# 8x3.net
KiCad netlist of a schematic drawn in Altium Designer
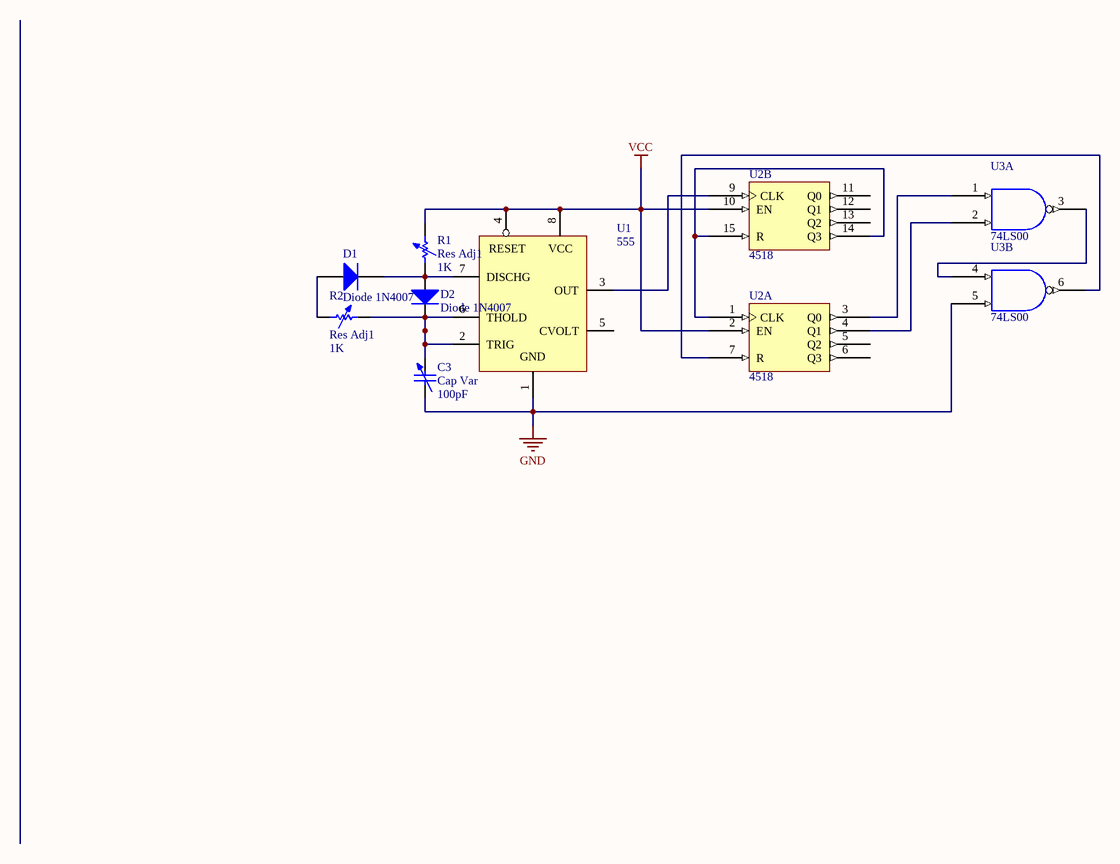
[diagram p0: 8x3.SchDoc]

(export (version "E")
  (design (tool "Eeschema 10.0.6"))
  (components
    (comp (ref "C3")
      (value "Cap Var")
      (footprint "C1210_N")
      (description "Variable or Adjustable Capacitor")
      (fields (field (name "ALTIUM_VALUE") "100pF") (field (name "PUBLISHER") "Altium Limited"))
      (libsource (lib "Miscellaneous Devices") (part "Cap Var"))
    )
    (comp (ref "D1")
      (value "Diode 1N4007")
      (footprint "DO-41")
      (description "1 Amp General Purpose Rectifier")
      (fields (field (name "PUBLISHER") "Altium Limited"))
      (libsource (lib "Miscellaneous Devices") (part "Diode 1N4007"))
    )
    (comp (ref "D2")
      (value "Diode 1N4007")
      (footprint "DO-41")
      (description "1 Amp General Purpose Rectifier")
      (fields (field (name "PUBLISHER") "Altium Limited"))
      (libsource (lib "Miscellaneous Devices") (part "Diode 1N4007"))
    )
    (comp (ref "R1")
      (value "Res Adj1")
      (footprint "AXIAL-0.7")
      (description "Variable Resistor")
      (fields (field (name "ALTIUM_VALUE") "1K") (field (name "PUBLISHER") "Altium Limited"))
      (libsource (lib "Miscellaneous Devices") (part "Res Adj1"))
    )
    (comp (ref "R2")
      (value "Res Adj1")
      (footprint "AXIAL-0.7")
      (description "Variable Resistor")
      (fields (field (name "ALTIUM_VALUE") "1K") (field (name "PUBLISHER") "Altium Limited"))
      (libsource (lib "Miscellaneous Devices") (part "Res Adj1"))
    )
    (comp (ref "U1") (value "555") (description "Timer") (libsource (lib "555") (part "555")))
    (comp (ref "U2") (value "4518") (footprint "DIP-16") (libsource (lib "CD4000系列IC") (part "4518")))
    (comp (ref "U3") (value "74LS00") (footprint "DIP-14") (libsource (lib "TTL74系列IC") (part "74LS00")))
  )
  (nets
    (net (code "1") (name "GND") (class "Default")
      (node (ref "C3") (pin "1") (pinfunction "1_1") (pintype "passive"))
      (node (ref "U1") (pin "1") (pinfunction "GND_1") (pintype "passive"))
      (node (ref "U2") (pin "8") (pinfunction "GND_8") (pintype "power_in"))
      (node (ref "U3") (pin "5") (pintype "input"))
      (node (ref "U3") (pin "7") (pinfunction "GND_7") (pintype "power_in"))
    )
    (net (code "2") (name "Net-(D1-A)") (class "Default")
      (node (ref "D1") (pin "1") (pinfunction "A_1") (pintype "passive"))
      (node (ref "R2") (pin "1") (pinfunction "1_1") (pintype "passive"))
    )
    (net (code "3") (name "Net-(D1-K)") (class "Default")
      (node (ref "D1") (pin "2") (pinfunction "K_2") (pintype "passive"))
      (node (ref "R1") (pin "1") (pinfunction "1_1") (pintype "passive"))
      (node (ref "U1") (pin "7") (pinfunction "DISCHG_7") (pintype "passive"))
    )
    (net (code "4") (name "Net-(D2-K)") (class "Default")
      (node (ref "C3") (pin "2") (pinfunction "2_2") (pintype "passive"))
      (node (ref "D2") (pin "2") (pinfunction "K_2") (pintype "passive"))
      (node (ref "R2") (pin "2") (pinfunction "2_2") (pintype "passive"))
      (node (ref "U1") (pin "2") (pinfunction "TRIG_2") (pintype "passive"))
      (node (ref "U1") (pin "6") (pinfunction "THOLD_6") (pintype "passive"))
    )
    (net (code "5") (name "Net-(U1-OUT)") (class "Default")
      (node (ref "U1") (pin "3") (pinfunction "OUT_3") (pintype "passive"))
      (node (ref "U2") (pin "9") (pinfunction "CLK_9") (pintype "input"))
    )
    (net (code "6") (name "Net-(U2A-CLK)") (class "Default")
      (node (ref "U2") (pin "1") (pinfunction "CLK_1") (pintype "input"))
      (node (ref "U2") (pin "14") (pinfunction "Q3_14") (pintype "output"))
      (node (ref "U2") (pin "15") (pinfunction "R_15") (pintype "input"))
    )
    (net (code "7") (name "Net-(U2A-Q0)") (class "Default")
      (node (ref "U2") (pin "3") (pinfunction "Q0_3") (pintype "output"))
      (node (ref "U3") (pin "1") (pintype "input"))
    )
    (net (code "8") (name "Net-(U2A-Q1)") (class "Default")
      (node (ref "U2") (pin "4") (pinfunction "Q1_4") (pintype "output"))
      (node (ref "U3") (pin "2") (pintype "input"))
    )
    (net (code "9") (name "Net-(U2A-R)") (class "Default")
      (node (ref "U2") (pin "7") (pinfunction "R_7") (pintype "input"))
      (node (ref "U3") (pin "6") (pintype "output"))
    )
    (net (code "10") (name "Net-(U3-Pad3)") (class "Default")
      (node (ref "U3") (pin "3") (pintype "output"))
      (node (ref "U3") (pin "4") (pintype "input"))
    )
    (net (code "11") (name "VCC") (class "Default")
      (node (ref "R1") (pin "2") (pinfunction "2_2") (pintype "passive"))
      (node (ref "U1") (pin "4") (pinfunction "RESET_4") (pintype "passive"))
      (node (ref "U1") (pin "8") (pinfunction "VCC_8") (pintype "passive"))
      (node (ref "U2") (pin "10") (pinfunction "EN_10") (pintype "input"))
      (node (ref "U2") (pin "16") (pinfunction "VCC_16") (pintype "power_in"))
      (node (ref "U2") (pin "2") (pinfunction "EN_2") (pintype "input"))
      (node (ref "U3") (pin "14") (pinfunction "VCC_14") (pintype "power_in"))
    )
    (net (code "12") (name "unconnected-(D2-A-Pad1)") (class "Default")
      (node (ref "D2") (pin "1") (pinfunction "A_1") (pintype "passive"))
    )
    (net (code "13") (name "unconnected-(U1-CVOLT-Pad5)") (class "Default")
      (node (ref "U1") (pin "5") (pinfunction "CVOLT_5") (pintype "passive"))
    )
    (net (code "14") (name "unconnected-(U2A-Q2-Pad5)") (class "Default")
      (node (ref "U2") (pin "5") (pinfunction "Q2_5") (pintype "output"))
    )
    (net (code "15") (name "unconnected-(U2A-Q3-Pad6)") (class "Default")
      (node (ref "U2") (pin "6") (pinfunction "Q3_6") (pintype "output"))
    )
    (net (code "16") (name "unconnected-(U2B-Q0-Pad11)") (class "Default")
      (node (ref "U2") (pin "11") (pinfunction "Q0_11") (pintype "output"))
    )
    (net (code "17") (name "unconnected-(U2B-Q1-Pad12)") (class "Default")
      (node (ref "U2") (pin "12") (pinfunction "Q1_12") (pintype "output"))
    )
    (net (code "18") (name "unconnected-(U2B-Q2-Pad13)") (class "Default")
      (node (ref "U2") (pin "13") (pinfunction "Q2_13") (pintype "output"))
    )
  )
)
